# motor_volt_sense.net
KiCad netlist of a schematic drawn in Altium Designer
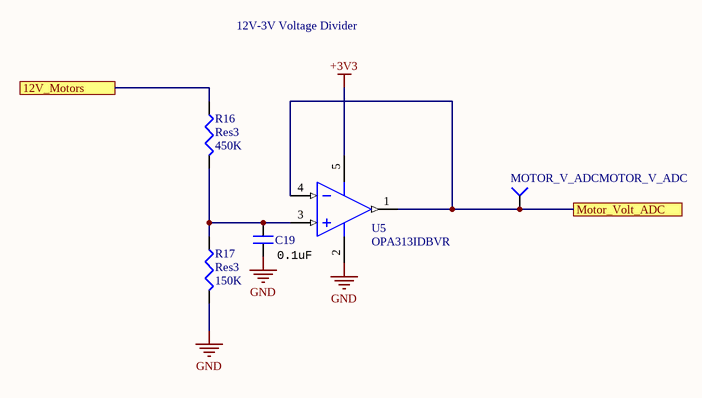
[diagram p0: motor_volt_sense.SchDoc]

(export (version "E")
  (design (tool "Eeschema 10.0.6"))
  (components
    (comp (ref "C19")
      (value "0.1uF")
      (footprint "CAPC0603(1608)55_N")
      (description "CAP CER 0.1UF 16V X7R 0603")
      (fields (field (name "MPN") "CC0603KRX7R7BB104") (field (name "MANUFACTURER") "Yageo"))
      (libsource (lib "*") (part "CAP_0.1uF_16V_0603"))
    )
    (comp (ref "MOTOR_V_ADCMOTOR_V_ADC")
      (value "MOTOR_V_ADC")
      (footprint "TESTPOINT")
      (description "TESTPOINT_SMD")
      (libsource (lib "UWRT_Schematic_Library_2020") (part "TESTPOINT_SMD"))
    )
    (comp (ref "R16")
      (value "Res3")
      (footprint "J1-0603")
      (description "Resistor")
      (fields (field (name "ALTIUM_VALUE") "450K") (field (name "PUBLISHER") "Altium Limited"))
      (libsource (lib "Miscellaneous Devices") (part "Res3"))
    )
    (comp (ref "R17")
      (value "Res3")
      (footprint "J1-0603")
      (description "Resistor")
      (fields (field (name "ALTIUM_VALUE") "150K") (field (name "PUBLISHER") "Altium Limited"))
      (libsource (lib "Miscellaneous Devices") (part "Res3"))
    )
    (comp (ref "U5")
      (value "OPA313IDBVR")
      (footprint "DBV0005A_M")
      (fields
        (field (name "MANUFACTURER") "Texas Instruments")
        (field (name "DIGI-KEY PART NUMBER") "296-35607-1-ND")
      )
      (libsource (lib "UWRT_Schematic_Library_2020") (part "OPAMP"))
    )
  )
  (nets
    (net (code "1") (name "+3V3") (class "Default")
      (node (ref "U5") (pin "5") (pinfunction "V+_5") (pintype "power_in"))
    )
    (net (code "2") (name "/12V_Motors") (class "Default")
      (node (ref "R16") (pin "1") (pinfunction "1_1") (pintype "passive"))
    )
    (net (code "3") (name "/Motor_Volt_ADC") (class "Default")
      (node (ref "MOTOR_V_ADCMOTOR_V_ADC") (pin "1") (pinfunction "=value_1") (pintype "passive"))
      (node (ref "U5") (pin "1") (pinfunction "OUT_1") (pintype "output"))
      (node (ref "U5") (pin "4") (pinfunction "IN-_4") (pintype "input"))
    )
    (net (code "4") (name "GND") (class "Default")
      (node (ref "C19") (pin "1") (pinfunction "1_1") (pintype "passive"))
      (node (ref "R17") (pin "2") (pinfunction "2_2") (pintype "passive"))
      (node (ref "U5") (pin "2") (pinfunction "V-_2") (pintype "power_in"))
    )
    (net (code "5") (name "Net-(U5-IN+)") (class "Default")
      (node (ref "C19") (pin "2") (pinfunction "2_2") (pintype "passive"))
      (node (ref "R16") (pin "2") (pinfunction "2_2") (pintype "passive"))
      (node (ref "R17") (pin "1") (pinfunction "1_1") (pintype "passive"))
      (node (ref "U5") (pin "3") (pinfunction "IN+_3") (pintype "input"))
    )
  )
)
